# sensor_board_v0_54.net
KiCad netlist of a schematic drawn in EAGLE
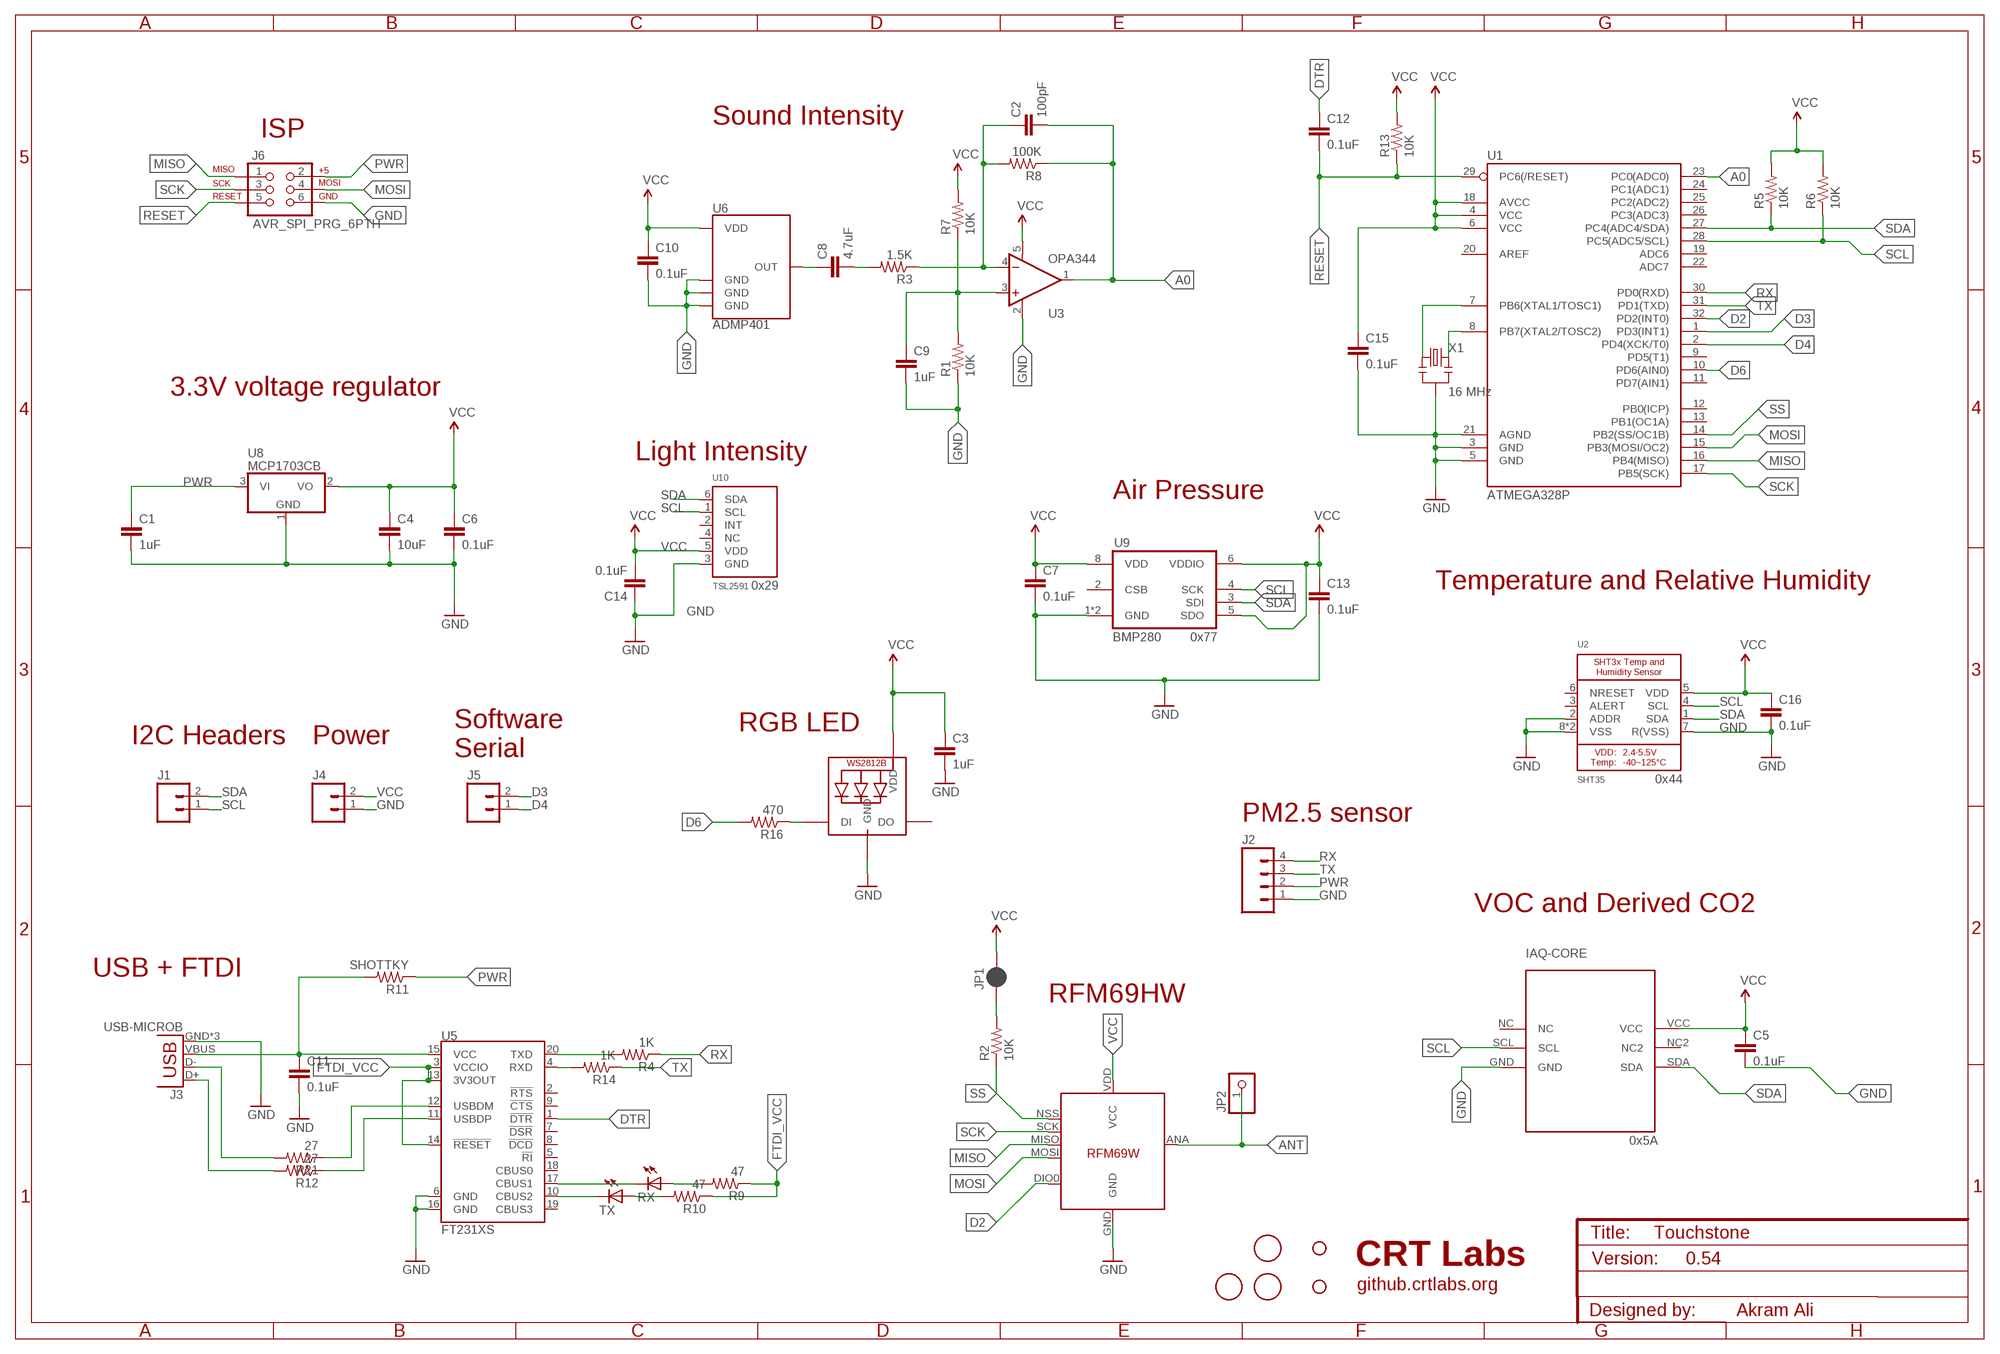
[diagram p0: schematic, sheet 1]

(export (version "E")
  (design (tool "Eeschema 10.0.6"))
  (components
    (comp (ref "C1")
      (value "1uF")
      (footprint "eagle-import:0805")
      (fields (field (name "MPN") "CC0805ZRY5V8BB105"))
      (libsource (lib "eagle-import") (part "CAP0805"))
    )
    (comp (ref "C2")
      (value "100pF")
      (footprint "eagle-import:0805")
      (fields (field (name "MPN") "CC0805JRNPOABN101"))
      (libsource (lib "eagle-import") (part "CAP0805"))
    )
    (comp (ref "C3")
      (value "1uF")
      (footprint "eagle-import:0805")
      (fields (field (name "MPN") "CC0805ZRY5V8BB105"))
      (libsource (lib "eagle-import") (part "CAP0805"))
    )
    (comp (ref "C4")
      (value "10uF")
      (footprint "eagle-import:0805")
      (fields (field (name "MPN") "CC0805KKX5R6BB106"))
      (libsource (lib "eagle-import") (part "CAP0805"))
    )
    (comp (ref "C5")
      (value "0.1uF")
      (footprint "eagle-import:0805")
      (fields (field (name "MPN") "CC0805KRX7R9BB104"))
      (libsource (lib "eagle-import") (part "SparkFun-Passives_CAP0805"))
    )
    (comp (ref "C6")
      (value "0.1uF")
      (footprint "eagle-import:0805")
      (fields (field (name "MPN") "CC0805KRX7R9BB104"))
      (libsource (lib "eagle-import") (part "CAP0805"))
    )
    (comp (ref "C7")
      (value "0.1uF")
      (footprint "eagle-import:0805")
      (fields (field (name "MPN") "CC0805KRX7R9BB104"))
      (libsource (lib "eagle-import") (part "SparkFun-Passives_CAP0805"))
    )
    (comp (ref "C8")
      (value "4.7uF")
      (footprint "eagle-import:0805")
      (fields (field (name "MPN") "CC0805KKX7R6BB475"))
      (libsource (lib "eagle-import") (part "CAP0805"))
    )
    (comp (ref "C9")
      (value "1uF")
      (footprint "eagle-import:0805")
      (fields (field (name "MPN") "CC0805ZRY5V8BB105"))
      (libsource (lib "eagle-import") (part "CAP0805"))
    )
    (comp (ref "C10")
      (value "0.1uF")
      (footprint "eagle-import:0805")
      (fields (field (name "MPN") "CC0805KRX7R9BB104"))
      (libsource (lib "eagle-import") (part "CAP0805"))
    )
    (comp (ref "C11")
      (value "0.1uF")
      (footprint "eagle-import:0805")
      (fields (field (name "MPN") "CC0805KRX7R9BB104"))
      (libsource (lib "eagle-import") (part "CAP0805"))
    )
    (comp (ref "C12")
      (value "0.1uF")
      (footprint "eagle-import:0805")
      (fields (field (name "MPN") "CC0805KRX7R9BB104"))
      (libsource (lib "eagle-import") (part "SparkFun-Passives_CAP0805"))
    )
    (comp (ref "C13")
      (value "0.1uF")
      (footprint "eagle-import:0805")
      (fields (field (name "MPN") "CC0805KRX7R9BB104"))
      (libsource (lib "eagle-import") (part "SparkFun-Passives_CAP0805"))
    )
    (comp (ref "C14")
      (value "0.1uF")
      (footprint "eagle-import:0805")
      (fields (field (name "MPN") "CC0805KRX7R9BB104"))
      (libsource (lib "eagle-import") (part "SparkFun-Passives_CAP0805"))
    )
    (comp (ref "C15")
      (value "0.1uF")
      (footprint "eagle-import:0805")
      (fields (field (name "MPN") "CC0805KRX7R9BB104"))
      (libsource (lib "eagle-import") (part "SparkFun-Passives_CAP0805"))
    )
    (comp (ref "C16")
      (value "0.1uF")
      (footprint "eagle-import:0805")
      (fields (field (name "MPN") "CC0805KRX7R9BB104"))
      (libsource (lib "eagle-import") (part "SparkFun-Passives_CAP0805"))
    )
    (comp (ref "H1")
      (value "STAND-OFF")
      (footprint "eagle-import:STAND-OFF")
      (libsource (lib "eagle-import") (part "STAND-OFF"))
    )
    (comp (ref "H2")
      (value "STAND-OFF")
      (footprint "eagle-import:STAND-OFF")
      (libsource (lib "eagle-import") (part "STAND-OFF"))
    )
    (comp (ref "IAQ-CORE")
      (value "IAQ-CORE")
      (footprint "eagle-import:IAQ-CORE")
      (fields (field (name "MPN") "IAQ-CORE C"))
      (libsource (lib "eagle-import") (part "IAQ-CORE"))
    )
    (comp (ref "J1")
      (value "M02PTH")
      (footprint "eagle-import:1X02")
      (libsource (lib "eagle-import") (part "M02PTH"))
    )
    (comp (ref "J2")
      (value "M04PTH")
      (footprint "eagle-import:1X04")
      (libsource (lib "eagle-import") (part "M04PTH"))
    )
    (comp (ref "J3")
      (value "USB-MICROB")
      (footprint "eagle-import:USB-MICROB")
      (fields (field (name "MPN") "47346-0001"))
      (libsource (lib "eagle-import") (part "USB-MICROB"))
    )
    (comp (ref "J4")
      (value "M02PTH")
      (footprint "eagle-import:1X02")
      (libsource (lib "eagle-import") (part "M02PTH"))
    )
    (comp (ref "J5")
      (value "M02PTH")
      (footprint "eagle-import:1X02")
      (libsource (lib "eagle-import") (part "M02PTH"))
    )
    (comp (ref "J6")
      (value "AVR_SPI_PRG_6PTH")
      (footprint "eagle-import:2X3")
      (libsource (lib "eagle-import") (part "AVR_SPI_PRG_6PTH"))
    )
    (comp (ref "JP1")
      (value "JUMPER-PAD-2-NC_BY_PASTEFULL-BOX-SILK")
      (footprint "eagle-import:PAD-JUMPER-2-NC_BY_PASTE_YES_SILK_FULL_BOX")
      (libsource (lib "eagle-import") (part "JUMPER-PAD-2-NC_BY_PASTEFULL-BOX-SILK"))
    )
    (comp (ref "JP2")
      (value "PINHD-1X1")
      (footprint "eagle-import:1X01")
      (libsource (lib "eagle-import") (part "PINHD-1X1"))
    )
    (comp (ref "LED1")
      (value "WS2812B3535")
      (footprint "eagle-import:LED3535")
      (fields (field (name "MPN") "SK6812 mini"))
      (libsource (lib "eagle-import") (part "WS2812B3535"))
    )
    (comp (ref "R1")
      (value "10K")
      (footprint "eagle-import:0805")
      (fields (field (name "MPN") "RC0805FR-0710KL"))
      (libsource (lib "eagle-import") (part "RESISTOR0805-RES"))
    )
    (comp (ref "R2")
      (value "10K")
      (footprint "eagle-import:0805")
      (fields (field (name "MPN") "RC0805FR-0710KL"))
      (libsource (lib "eagle-import") (part "RESISTOR0805-RES"))
    )
    (comp (ref "R3")
      (value "1.5K")
      (footprint "eagle-import:0805")
      (fields (field (name "MPN") "RC0805FR-071K5L "))
      (libsource (lib "eagle-import") (part "RESISTOR0805-RES"))
    )
    (comp (ref "R4")
      (value "1K")
      (footprint "eagle-import:0805")
      (fields (field (name "MPN") "RC0805FR-071KL"))
      (libsource (lib "eagle-import") (part "RESISTOR0805-RES"))
    )
    (comp (ref "R5")
      (value "10K")
      (footprint "eagle-import:0805")
      (fields (field (name "MPN") "RC0805FR-0710KL"))
      (libsource (lib "eagle-import") (part "SparkFun-Resistors_RESISTOR0805-RES"))
    )
    (comp (ref "R6")
      (value "10K")
      (footprint "eagle-import:0805")
      (fields (field (name "MPN") "RC0805FR-0710KL"))
      (libsource (lib "eagle-import") (part "SparkFun-Resistors_RESISTOR0805-RES"))
    )
    (comp (ref "R7")
      (value "10K")
      (footprint "eagle-import:0805")
      (fields (field (name "MPN") "RC0805FR-0710KL"))
      (libsource (lib "eagle-import") (part "RESISTOR0805-RES"))
    )
    (comp (ref "R8")
      (value "100K")
      (footprint "eagle-import:0805")
      (fields (field (name "MPN") "RC0805FR-07100KL "))
      (libsource (lib "eagle-import") (part "RESISTOR0805-RES"))
    )
    (comp (ref "R9")
      (value "47")
      (footprint "eagle-import:0805")
      (fields (field (name "MPN") "RC0805FR-0747RL "))
      (libsource (lib "eagle-import") (part "RESISTOR0805-RES"))
    )
    (comp (ref "R10")
      (value "47")
      (footprint "eagle-import:0805")
      (fields (field (name "MPN") "RC0805FR-0747RL "))
      (libsource (lib "eagle-import") (part "RESISTOR0805-RES"))
    )
    (comp (ref "R11")
      (value "SHOTTKY")
      (footprint "eagle-import:0805")
      (fields (field (name "MPN") "SD0805S040S0R5"))
      (libsource (lib "eagle-import") (part "RESISTOR0805-RES"))
    )
    (comp (ref "R12")
      (value "27")
      (footprint "eagle-import:0805")
      (fields (field (name "MPN") "RC0805FR-0727RL "))
      (libsource (lib "eagle-import") (part "RESISTOR0805-RES"))
    )
    (comp (ref "R13")
      (value "10K")
      (footprint "eagle-import:0805")
      (fields (field (name "MPN") "RC0805FR-0710KL"))
      (libsource (lib "eagle-import") (part "RESISTOR0805-RES"))
    )
    (comp (ref "R14")
      (value "1K")
      (footprint "eagle-import:0805")
      (fields (field (name "MPN") "RC0805FR-071KL"))
      (libsource (lib "eagle-import") (part "RESISTOR0805-RES"))
    )
    (comp (ref "R16")
      (value "470")
      (footprint "eagle-import:R0603")
      (fields (field (name "MPN") "RC0805FR-07470RL "))
      (libsource (lib "eagle-import") (part "R-US_R0603"))
    )
    (comp (ref "R21")
      (value "27")
      (footprint "eagle-import:0805")
      (fields (field (name "MPN") "RC0805FR-0727RL "))
      (libsource (lib "eagle-import") (part "RESISTOR0805-RES"))
    )
    (comp (ref "RX")
      (value "LEDCHIPLED_0805")
      (footprint "eagle-import:CHIPLED_0805")
      (fields (field (name "MPN") "LG R971-KN-1"))
      (libsource (lib "eagle-import") (part "LEDCHIPLED_0805"))
    )
    (comp (ref "TX")
      (value "LEDCHIPLED_0805")
      (footprint "eagle-import:CHIPLED_0805")
      (fields (field (name "MPN") "LG R971-KN-1"))
      (libsource (lib "eagle-import") (part "LEDCHIPLED_0805"))
    )
    (comp (ref "U$1")
      (value "FIDUCIAL")
      (footprint "eagle-import:FIDUCIAL_1MM")
      (libsource (lib "eagle-import") (part "FIDUCIAL"))
    )
    (comp (ref "U$2")
      (value "FIDUCIAL")
      (footprint "eagle-import:FIDUCIAL_1MM")
      (libsource (lib "eagle-import") (part "FIDUCIAL"))
    )
    (comp (ref "U$3")
      (value "FIDUCIAL")
      (footprint "eagle-import:FIDUCIAL_1MM")
      (libsource (lib "eagle-import") (part "FIDUCIAL"))
    )
    (comp (ref "U1")
      (value "ATMEGA328P")
      (footprint "eagle-import:TQFP32-08")
      (fields (field (name "MPN") "ATMEGA328PB-AU"))
      (libsource (lib "eagle-import") (part "ATMEGA328P_TQFP"))
    )
    (comp (ref "U2")
      (value "SHT35")
      (footprint "eagle-import:SHT3X")
      (fields (field (name "MPN") "SHT35-DIS-B"))
      (libsource (lib "eagle-import") (part "SHT3X"))
    )
    (comp (ref "U3")
      (value "OPA344")
      (footprint "eagle-import:SOT23-5")
      (fields (field (name "MPN") "OPA344NA/3K"))
      (libsource (lib "eagle-import") (part "OPA344"))
    )
    (comp (ref "U4")
      (value "RFM69HW")
      (footprint "eagle-import:LOWPOWERLAB_RFM69W-MINPADS")
      (libsource (lib "eagle-import") (part "LOWPOWERLAB_RFM69"))
    )
    (comp (ref "U5")
      (value "FT231XS")
      (footprint "eagle-import:SSOP20_L")
      (fields (field (name "MPN") "FT231XQ-R"))
      (libsource (lib "eagle-import") (part "FT231XS"))
    )
    (comp (ref "U6")
      (value "ADMP401")
      (footprint "eagle-import:ADMP401")
      (fields (field (name "MPN") "INMP401ACEZ-R7"))
      (libsource (lib "eagle-import") (part "ADMP401"))
    )
    (comp (ref "U8")
      (value "MCP1703CB")
      (footprint "eagle-import:SOT23")
      (fields (field (name "MPN") "MCP1703T-2502E/CB"))
      (libsource (lib "eagle-import") (part "MCP1703CB"))
    )
    (comp (ref "U9")
      (value "BMP280")
      (footprint "eagle-import:BMP280")
      (libsource (lib "eagle-import") (part "BMP280"))
    )
    (comp (ref "U10")
      (value "TSL2591")
      (footprint "eagle-import:DFN6_TAOS")
      (fields (field (name "MPN") "TSL25911FN "))
      (libsource (lib "eagle-import") (part "LIGHT_TSL2591"))
    )
    (comp (ref "X1")
      (value "16 MHz")
      (footprint "eagle-import:RESONATOR-SMD")
      (libsource (lib "eagle-import") (part "RESONATORSMD"))
    )
  )
  (nets
    (net (code "1") (name "A0") (class "Default")
      (node (ref "C2") (pin "2") (pinfunction "2_2") (pintype "passive"))
      (node (ref "R8") (pin "1") (pinfunction "1_1") (pintype "passive"))
      (node (ref "U1") (pin "23") (pinfunction "PC0(ADC0)_23") (pintype "bidirectional"))
      (node (ref "U3") (pin "1") (pinfunction "OUT_1") (pintype "output"))
    )
    (net (code "2") (name "ANT") (class "Default")
      (node (ref "JP2") (pin "1") (pinfunction "1_1") (pintype "passive"))
      (node (ref "U4") (pin "ANA") (pinfunction "ANT_ANA") (pintype "passive"))
    )
    (net (code "3") (name "D2") (class "Default")
      (node (ref "U1") (pin "32") (pinfunction "PD2(INT0)_32") (pintype "bidirectional"))
      (node (ref "U4") (pin "DIO0") (pinfunction "DIO0_DIO0") (pintype "open_collector"))
    )
    (net (code "4") (name "D3") (class "Default")
      (node (ref "J5") (pin "2") (pinfunction "2_2") (pintype "passive"))
      (node (ref "U1") (pin "1") (pinfunction "PD3(INT1)_1") (pintype "bidirectional"))
    )
    (net (code "5") (name "D4") (class "Default")
      (node (ref "J5") (pin "1") (pinfunction "1_1") (pintype "passive"))
      (node (ref "U1") (pin "2") (pinfunction "PD4(XCK/T0)_2") (pintype "bidirectional"))
    )
    (net (code "6") (name "D6") (class "Default")
      (node (ref "R16") (pin "2") (pinfunction "2_2") (pintype "passive"))
      (node (ref "U1") (pin "10") (pinfunction "PD6(AIN0)_10") (pintype "bidirectional"))
    )
    (net (code "7") (name "DTR") (class "Default")
      (node (ref "C12") (pin "1") (pinfunction "1_1") (pintype "passive"))
      (node (ref "U5") (pin "1") (pinfunction "~{DTR}_1") (pintype "bidirectional"))
    )
    (net (code "8") (name "FTDI_VCC") (class "Default")
      (node (ref "R10") (pin "1") (pinfunction "1_1") (pintype "passive"))
      (node (ref "R9") (pin "1") (pinfunction "1_1") (pintype "passive"))
      (node (ref "U5") (pin "13") (pinfunction "3V3OUT_13") (pintype "bidirectional"))
      (node (ref "U5") (pin "14") (pinfunction "~{RESET}_14") (pintype "bidirectional"))
      (node (ref "U5") (pin "3") (pinfunction "VCCIO_3") (pintype "bidirectional"))
    )
    (net (code "9") (name "GND") (class "Default")
      (node (ref "C1") (pin "2") (pinfunction "2_2") (pintype "passive"))
      (node (ref "C10") (pin "2") (pinfunction "2_2") (pintype "passive"))
      (node (ref "C11") (pin "2") (pinfunction "2_2") (pintype "passive"))
      (node (ref "C13") (pin "2") (pinfunction "2_2") (pintype "passive"))
      (node (ref "C14") (pin "1") (pinfunction "1_1") (pintype "passive"))
      (node (ref "C15") (pin "2") (pinfunction "2_2") (pintype "passive"))
      (node (ref "C16") (pin "2") (pinfunction "2_2") (pintype "passive"))
      (node (ref "C3") (pin "2") (pinfunction "2_2") (pintype "passive"))
      (node (ref "C4") (pin "2") (pinfunction "2_2") (pintype "passive"))
      (node (ref "C5") (pin "2") (pinfunction "2_2") (pintype "passive"))
      (node (ref "C6") (pin "2") (pinfunction "2_2") (pintype "passive"))
      (node (ref "C7") (pin "2") (pinfunction "2_2") (pintype "passive"))
      (node (ref "C9") (pin "2") (pinfunction "2_2") (pintype "passive"))
      (node (ref "IAQ-CORE") (pin "GND") (pinfunction "GND_GND") (pintype "bidirectional"))
      (node (ref "J2") (pin "1") (pinfunction "1_1") (pintype "passive"))
      (node (ref "J3") (pin "GND") (pinfunction "GND_GND") (pintype "bidirectional"))
      (node (ref "J3") (pin "MT1") (pinfunction "GND_MT1") (pintype "bidirectional"))
      (node (ref "J3") (pin "MT2") (pinfunction "GND_MT2") (pintype "bidirectional"))
      (node (ref "J4") (pin "1") (pinfunction "1_1") (pintype "passive"))
      (node (ref "J6") (pin "6") (pinfunction "6_6") (pintype "passive"))
      (node (ref "LED1") (pin "4") (pinfunction "GND_4") (pintype "power_in"))
      (node (ref "R1") (pin "1") (pinfunction "1_1") (pintype "passive"))
      (node (ref "U1") (pin "21") (pinfunction "AGND_21") (pintype "bidirectional"))
      (node (ref "U1") (pin "3") (pinfunction "GND_3") (pintype "bidirectional"))
      (node (ref "U1") (pin "5") (pinfunction "GND_5") (pintype "bidirectional"))
      (node (ref "U10") (pin "3") (pinfunction "GND_3") (pintype "power_in"))
      (node (ref "U2") (pin "2") (pinfunction "ADDR_2") (pintype "bidirectional"))
      (node (ref "U2") (pin "7") (pinfunction "R(VSS)_7") (pintype "bidirectional"))
      (node (ref "U2") (pin "8") (pinfunction "VSS_8") (pintype "power_in"))
      (node (ref "U2") (pin "THERMAL") (pinfunction "VSS_THERMAL") (pintype "power_in"))
      (node (ref "U3") (pin "2") (pinfunction "V-_2") (pintype "power_in"))
      (node (ref "U4") (pin "GND") (pinfunction "GND_GND") (pintype "power_in"))
      (node (ref "U5") (pin "16") (pinfunction "GND_16") (pintype "bidirectional"))
      (node (ref "U5") (pin "6") (pinfunction "GND_6") (pintype "bidirectional"))
      (node (ref "U6") (pin "2") (pinfunction "GND_2") (pintype "bidirectional"))
      (node (ref "U6") (pin "4") (pinfunction "GND_4") (pintype "bidirectional"))
      (node (ref "U6") (pin "6") (pinfunction "GND_6") (pintype "bidirectional"))
      (node (ref "U8") (pin "1") (pinfunction "GND_1") (pintype "passive"))
      (node (ref "U9") (pin "1") (pinfunction "GND_1") (pintype "power_in"))
      (node (ref "U9") (pin "7") (pinfunction "GND_7") (pintype "power_in"))
      (node (ref "X1") (pin "2") (pinfunction "2_2") (pintype "passive"))
    )
    (net (code "10") (name "MISO") (class "Default")
      (node (ref "J6") (pin "1") (pinfunction "1_1") (pintype "passive"))
      (node (ref "U1") (pin "16") (pinfunction "PB4(MISO)_16") (pintype "bidirectional"))
      (node (ref "U4") (pin "MISO") (pinfunction "MISO_MISO") (pintype "input"))
    )
    (net (code "11") (name "MOSI") (class "Default")
      (node (ref "J6") (pin "4") (pinfunction "4_4") (pintype "passive"))
      (node (ref "U1") (pin "15") (pinfunction "PB3(MOSI/OC2)_15") (pintype "bidirectional"))
      (node (ref "U4") (pin "MOSI") (pinfunction "MOSI_MOSI") (pintype "output"))
    )
    (net (code "12") (name "Net-(C8-Pad2)") (class "Default")
      (node (ref "C8") (pin "2") (pinfunction "2_2") (pintype "passive"))
      (node (ref "R3") (pin "2") (pinfunction "2_2") (pintype "passive"))
    )
    (net (code "13") (name "Net-(J3-PadD+)") (class "Default")
      (node (ref "J3") (pin "D+") (pinfunction "D+_D+") (pintype "bidirectional"))
      (node (ref "R12") (pin "2") (pinfunction "2_2") (pintype "passive"))
    )
    (net (code "14") (name "Net-(J3-PadD-)") (class "Default")
      (node (ref "J3") (pin "D-") (pinfunction "D-_D-") (pintype "bidirectional"))
      (node (ref "R21") (pin "2") (pinfunction "2_2") (pintype "passive"))
    )
    (net (code "15") (name "Net-(JP1-Pad1)") (class "Default")
      (node (ref "JP1") (pin "1") (pinfunction "1_1") (pintype "passive"))
      (node (ref "R2") (pin "2") (pinfunction "2_2") (pintype "passive"))
    )
    (net (code "16") (name "Net-(LED1-DI)") (class "Default")
      (node (ref "LED1") (pin "1") (pinfunction "DI_1") (pintype "input"))
      (node (ref "R16") (pin "1") (pinfunction "1_1") (pintype "passive"))
    )
    (net (code "17") (name "Net-(R9-Pad2)") (class "Default")
      (node (ref "R9") (pin "2") (pinfunction "2_2") (pintype "passive"))
      (node (ref "RX") (pin "A") (pinfunction "A_A") (pintype "passive"))
    )
    (net (code "18") (name "Net-(R10-Pad2)") (class "Default")
      (node (ref "R10") (pin "2") (pinfunction "2_2") (pintype "passive"))
      (node (ref "TX") (pin "A") (pinfunction "A_A") (pintype "passive"))
    )
    (net (code "19") (name "Net-(U1-PB6(XTAL1{slash}TOSC1))") (class "Default")
      (node (ref "U1") (pin "7") (pinfunction "PB6(XTAL1/TOSC1)_7") (pintype "bidirectional"))
      (node (ref "X1") (pin "1") (pinfunction "1_1") (pintype "passive"))
    )
    (net (code "20") (name "Net-(U1-PB7(XTAL2{slash}TOSC2))") (class "Default")
      (node (ref "U1") (pin "8") (pinfunction "PB7(XTAL2/TOSC2)_8") (pintype "bidirectional"))
      (node (ref "X1") (pin "3") (pinfunction "3_3") (pintype "passive"))
    )
    (net (code "21") (name "Net-(U3-+IN)") (class "Default")
      (node (ref "C9") (pin "1") (pinfunction "1_1") (pintype "passive"))
      (node (ref "R1") (pin "2") (pinfunction "2_2") (pintype "passive"))
      (node (ref "R7") (pin "1") (pinfunction "1_1") (pintype "passive"))
      (node (ref "U3") (pin "3") (pinfunction "+IN_3") (pintype "input"))
    )
    (net (code "22") (name "Net-(U3--IN)") (class "Default")
      (node (ref "C2") (pin "1") (pinfunction "1_1") (pintype "passive"))
      (node (ref "R3") (pin "1") (pinfunction "1_1") (pintype "passive"))
      (node (ref "R8") (pin "2") (pinfunction "2_2") (pintype "passive"))
      (node (ref "U3") (pin "4") (pinfunction "-IN_4") (pintype "input"))
    )
    (net (code "23") (name "Net-(U5-CBUS1)") (class "Default")
      (node (ref "RX") (pin "C") (pinfunction "C_C") (pintype "passive"))
      (node (ref "U5") (pin "17") (pinfunction "CBUS1_17") (pintype "bidirectional"))
    )
    (net (code "24") (name "Net-(U5-CBUS2)") (class "Default")
      (node (ref "TX") (pin "C") (pinfunction "C_C") (pintype "passive"))
      (node (ref "U5") (pin "10") (pinfunction "CBUS2_10") (pintype "bidirectional"))
    )
    (net (code "25") (name "Net-(U5-RXD)") (class "Default")
      (node (ref "R14") (pin "2") (pinfunction "2_2") (pintype "passive"))
      (node (ref "U5") (pin "4") (pinfunction "RXD_4") (pintype "bidirectional"))
    )
    (net (code "26") (name "Net-(U5-TXD)") (class "Default")
      (node (ref "R4") (pin "2") (pinfunction "2_2") (pintype "passive"))
      (node (ref "U5") (pin "20") (pinfunction "TXD_20") (pintype "bidirectional"))
    )
    (net (code "27") (name "Net-(U5-USBDM)") (class "Default")
      (node (ref "R21") (pin "1") (pinfunction "1_1") (pintype "passive"))
      (node (ref "U5") (pin "12") (pinfunction "USBDM_12") (pintype "bidirectional"))
    )
    (net (code "28") (name "Net-(U5-USBDP)") (class "Default")
      (node (ref "R12") (pin "1") (pinfunction "1_1") (pintype "passive"))
      (node (ref "U5") (pin "11") (pinfunction "USBDP_11") (pintype "bidirectional"))
    )
    (net (code "29") (name "Net-(U5-VCC)") (class "Default")
      (node (ref "C11") (pin "1") (pinfunction "1_1") (pintype "passive"))
      (node (ref "J3") (pin "VBUS") (pinfunction "VBUS_VBUS") (pintype "bidirectional"))
      (node (ref "R11") (pin "2") (pinfunction "2_2") (pintype "passive"))
      (node (ref "U5") (pin "15") (pinfunction "VCC_15") (pintype "bidirectional"))
    )
    (net (code "30") (name "Net-(U6-OUT)") (class "Default")
      (node (ref "C8") (pin "1") (pinfunction "1_1") (pintype "passive"))
      (node (ref "U6") (pin "1") (pinfunction "OUT_1") (pintype "bidirectional"))
    )
    (net (code "31") (name "PWR") (class "Default")
      (node (ref "C1") (pin "1") (pinfunction "1_1") (pintype "passive"))
      (node (ref "J2") (pin "2") (pinfunction "2_2") (pintype "passive"))
      (node (ref "J6") (pin "2") (pinfunction "2_2") (pintype "passive"))
      (node (ref "R11") (pin "1") (pinfunction "1_1") (pintype "passive"))
      (node (ref "U8") (pin "3") (pinfunction "VI_3") (pintype "input"))
    )
    (net (code "32") (name "RESET") (class "Default")
      (node (ref "C12") (pin "2") (pinfunction "2_2") (pintype "passive"))
      (node (ref "J6") (pin "5") (pinfunction "5_5") (pintype "passive"))
      (node (ref "R13") (pin "1") (pinfunction "1_1") (pintype "passive"))
      (node (ref "U1") (pin "29") (pinfunction "PC6(/RESET)_29") (pintype "bidirectional"))
    )
    (net (code "33") (name "RX") (class "Default")
      (node (ref "J2") (pin "4") (pinfunction "4_4") (pintype "passive"))
      (node (ref "R4") (pin "1") (pinfunction "1_1") (pintype "passive"))
      (node (ref "U1") (pin "30") (pinfunction "PD0(RXD)_30") (pintype "bidirectional"))
    )
    (net (code "34") (name "SCK") (class "Default")
      (node (ref "J6") (pin "3") (pinfunction "3_3") (pintype "passive"))
      (node (ref "U1") (pin "17") (pinfunction "PB5(SCK)_17") (pintype "bidirectional"))
      (node (ref "U4") (pin "SCK") (pinfunction "SCK_SCK") (pintype "input"))
    )
    (net (code "35") (name "SCL") (class "Default")
      (node (ref "IAQ-CORE") (pin "SCL") (pinfunction "SCL_SCL") (pintype "bidirectional"))
      (node (ref "J1") (pin "1") (pinfunction "1_1") (pintype "passive"))
      (node (ref "R6") (pin "1") (pinfunction "1_1") (pintype "passive"))
      (node (ref "U1") (pin "28") (pinfunction "PC5(ADC5/SCL)_28") (pintype "bidirectional"))
      (node (ref "U10") (pin "1") (pinfunction "SCL_1") (pintype "bidirectional"))
      (node (ref "U2") (pin "4") (pinfunction "SCL_4") (pintype "bidirectional"))
      (node (ref "U9") (pin "4") (pinfunction "SCK_4") (pintype "bidirectional"))
    )
    (net (code "36") (name "SDA") (class "Default")
      (node (ref "IAQ-CORE") (pin "SDA") (pinfunction "SDA_SDA") (pintype "bidirectional"))
      (node (ref "J1") (pin "2") (pinfunction "2_2") (pintype "passive"))
      (node (ref "R5") (pin "1") (pinfunction "1_1") (pintype "passive"))
      (node (ref "U1") (pin "27") (pinfunction "PC4(ADC4/SDA)_27") (pintype "bidirectional"))
      (node (ref "U10") (pin "6") (pinfunction "SDA_6") (pintype "bidirectional"))
      (node (ref "U2") (pin "1") (pinfunction "SDA_1") (pintype "bidirectional"))
      (node (ref "U9") (pin "3") (pinfunction "SDI_3") (pintype "bidirectional"))
    )
    (net (code "37") (name "SS") (class "Default")
      (node (ref "R2") (pin "1") (pinfunction "1_1") (pintype "passive"))
      (node (ref "U1") (pin "14") (pinfunction "PB2(SS/OC1B)_14") (pintype "bidirectional"))
      (node (ref "U4") (pin "NSS") (pinfunction "SEL_NSS") (pintype "input"))
    )
    (net (code "38") (name "TX") (class "Default")
      (node (ref "J2") (pin "3") (pinfunction "3_3") (pintype "passive"))
      (node (ref "R14") (pin "1") (pinfunction "1_1") (pintype "passive"))
      (node (ref "U1") (pin "31") (pinfunction "PD1(TXD)_31") (pintype "bidirectional"))
    )
    (net (code "39") (name "VCC") (class "Default")
      (node (ref "C10") (pin "1") (pinfunction "1_1") (pintype "passive"))
      (node (ref "C13") (pin "1") (pinfunction "1_1") (pintype "passive"))
      (node (ref "C14") (pin "2") (pinfunction "2_2") (pintype "passive"))
      (node (ref "C15") (pin "1") (pinfunction "1_1") (pintype "passive"))
      (node (ref "C16") (pin "1") (pinfunction "1_1") (pintype "passive"))
      (node (ref "C3") (pin "1") (pinfunction "1_1") (pintype "passive"))
      (node (ref "C4") (pin "1") (pinfunction "1_1") (pintype "passive"))
      (node (ref "C5") (pin "1") (pinfunction "1_1") (pintype "passive"))
      (node (ref "C6") (pin "1") (pinfunction "1_1") (pintype "passive"))
      (node (ref "C7") (pin "1") (pinfunction "1_1") (pintype "passive"))
      (node (ref "IAQ-CORE") (pin "VCC") (pinfunction "VCC_VCC") (pintype "bidirectional"))
      (node (ref "J4") (pin "2") (pinfunction "2_2") (pintype "passive"))
      (node (ref "JP1") (pin "2") (pinfunction "2_2") (pintype "passive"))
      (node (ref "LED1") (pin "2") (pinfunction "VDD_2") (pintype "power_in"))
      (node (ref "R13") (pin "2") (pinfunction "2_2") (pintype "passive"))
      (node (ref "R5") (pin "2") (pinfunction "2_2") (pintype "passive"))
      (node (ref "R6") (pin "2") (pinfunction "2_2") (pintype "passive"))
      (node (ref "R7") (pin "2") (pinfunction "2_2") (pintype "passive"))
      (node (ref "U1") (pin "18") (pinfunction "AVCC_18") (pintype "bidirectional"))
      (node (ref "U1") (pin "4") (pinfunction "VCC_4") (pintype "bidirectional"))
      (node (ref "U1") (pin "6") (pinfunction "VCC_6") (pintype "bidirectional"))
      (node (ref "U10") (pin "5") (pinfunction "VDD_5") (pintype "power_in"))
      (node (ref "U2") (pin "5") (pinfunction "VDD_5") (pintype "power_in"))
      (node (ref "U3") (pin "5") (pinfunction "V+_5") (pintype "power_in"))
      (node (ref "U4") (pin "VDD") (pinfunction "VCC_VDD") (pintype "power_in"))
      (node (ref "U6") (pin "5") (pinfunction "VDD_5") (pintype "bidirectional"))
      (node (ref "U8") (pin "2") (pinfunction "VO_2") (pintype "passive"))
      (node (ref "U9") (pin "5") (pinfunction "SDO_5") (pintype "input"))
      (node (ref "U9") (pin "6") (pinfunction "VDDIO_6") (pintype "power_in"))
      (node (ref "U9") (pin "8") (pinfunction "VDD_8") (pintype "power_in"))
    )
    (net (code "40") (name "unconnected-(IAQ-CORE-PadNC)") (class "Default")
      (node (ref "IAQ-CORE") (pin "NC") (pinfunction "NC_NC") (pintype "bidirectional"))
    )
    (net (code "41") (name "unconnected-(IAQ-CORE-PadNC2)") (class "Default")
      (node (ref "IAQ-CORE") (pin "NC2") (pinfunction "NC2_NC2") (pintype "bidirectional"))
    )
    (net (code "42") (name "unconnected-(LED1-DO-Pad3)") (class "Default")
      (node (ref "LED1") (pin "3") (pinfunction "DO_3") (pintype "output"))
    )
    (net (code "43") (name "unconnected-(U1-ADC6-Pad19)") (class "Default")
      (node (ref "U1") (pin "19") (pinfunction "ADC6_19") (pintype "bidirectional"))
    )
    (net (code "44") (name "unconnected-(U1-ADC7-Pad22)") (class "Default")
      (node (ref "U1") (pin "22") (pinfunction "ADC7_22") (pintype "bidirectional"))
    )
    (net (code "45") (name "unconnected-(U1-AREF-Pad20)") (class "Default")
      (node (ref "U1") (pin "20") (pinfunction "AREF_20") (pintype "bidirectional"))
    )
    (net (code "46") (name "unconnected-(U1-PB0(ICP)-Pad12)") (class "Default")
      (node (ref "U1") (pin "12") (pinfunction "PB0(ICP)_12") (pintype "bidirectional"))
    )
    (net (code "47") (name "unconnected-(U1-PB1(OC1A)-Pad13)") (class "Default")
      (node (ref "U1") (pin "13") (pinfunction "PB1(OC1A)_13") (pintype "bidirectional"))
    )
    (net (code "48") (name "unconnected-(U1-PC1(ADC1)-Pad24)") (class "Default")
      (node (ref "U1") (pin "24") (pinfunction "PC1(ADC1)_24") (pintype "bidirectional"))
    )
    (net (code "49") (name "unconnected-(U1-PC2(ADC2)-Pad25)") (class "Default")
      (node (ref "U1") (pin "25") (pinfunction "PC2(ADC2)_25") (pintype "bidirectional"))
    )
    (net (code "50") (name "unconnected-(U1-PC3(ADC3)-Pad26)") (class "Default")
      (node (ref "U1") (pin "26") (pinfunction "PC3(ADC3)_26") (pintype "bidirectional"))
    )
    (net (code "51") (name "unconnected-(U1-PD5(T1)-Pad9)") (class "Default")
      (node (ref "U1") (pin "9") (pinfunction "PD5(T1)_9") (pintype "bidirectional"))
    )
    (net (code "52") (name "unconnected-(U1-PD7(AIN1)-Pad11)") (class "Default")
      (node (ref "U1") (pin "11") (pinfunction "PD7(AIN1)_11") (pintype "bidirectional"))
    )
    (net (code "53") (name "unconnected-(U2-ALERT-Pad3)") (class "Default")
      (node (ref "U2") (pin "3") (pinfunction "ALERT_3") (pintype "bidirectional"))
    )
    (net (code "54") (name "unconnected-(U2-NRESET-Pad6)") (class "Default")
      (node (ref "U2") (pin "6") (pinfunction "NRESET_6") (pintype "bidirectional"))
    )
    (net (code "55") (name "unconnected-(U5-CBUS0-Pad18)") (class "Default")
      (node (ref "U5") (pin "18") (pinfunction "CBUS0_18") (pintype "bidirectional"))
    )
    (net (code "56") (name "unconnected-(U5-CBUS3-Pad19)") (class "Default")
      (node (ref "U5") (pin "19") (pinfunction "CBUS3_19") (pintype "bidirectional"))
    )
    (net (code "57") (name "unconnected-(U5-~{CTS}-Pad9)") (class "Default")
      (node (ref "U5") (pin "9") (pinfunction "~{CTS}_9") (pintype "bidirectional"))
    )
    (net (code "58") (name "unconnected-(U5-~{DCD}-Pad8)") (class "Default")
      (node (ref "U5") (pin "8") (pinfunction "~{DCD}_8") (pintype "bidirectional"))
    )
    (net (code "59") (name "unconnected-(U5-~{DSR}-Pad7)") (class "Default")
      (node (ref "U5") (pin "7") (pinfunction "~{DSR}_7") (pintype "bidirectional"))
    )
    (net (code "60") (name "unconnected-(U5-~{RI}-Pad5)") (class "Default")
      (node (ref "U5") (pin "5") (pinfunction "~{RI}_5") (pintype "bidirectional"))
    )
    (net (code "61") (name "unconnected-(U5-~{RTS}-Pad2)") (class "Default")
      (node (ref "U5") (pin "2") (pinfunction "~{RTS}_2") (pintype "bidirectional"))
    )
    (net (code "62") (name "unconnected-(U9-CSB-Pad2)") (class "Default")
      (node (ref "U9") (pin "2") (pinfunction "CSB_2") (pintype "input"))
    )
    (net (code "63") (name "unconnected-(U10-INT-Pad2)") (class "Default")
      (node (ref "U10") (pin "2") (pinfunction "INT_2") (pintype "output"))
    )
    (net (code "64") (name "unconnected-(U10-NC-Pad4)") (class "Default")
      (node (ref "U10") (pin "4") (pinfunction "NC_4") (pintype "no_connect"))
    )
  )
)
